# sistem_minimum_Atmega8.net
KiCad netlist of a schematic drawn in EAGLE
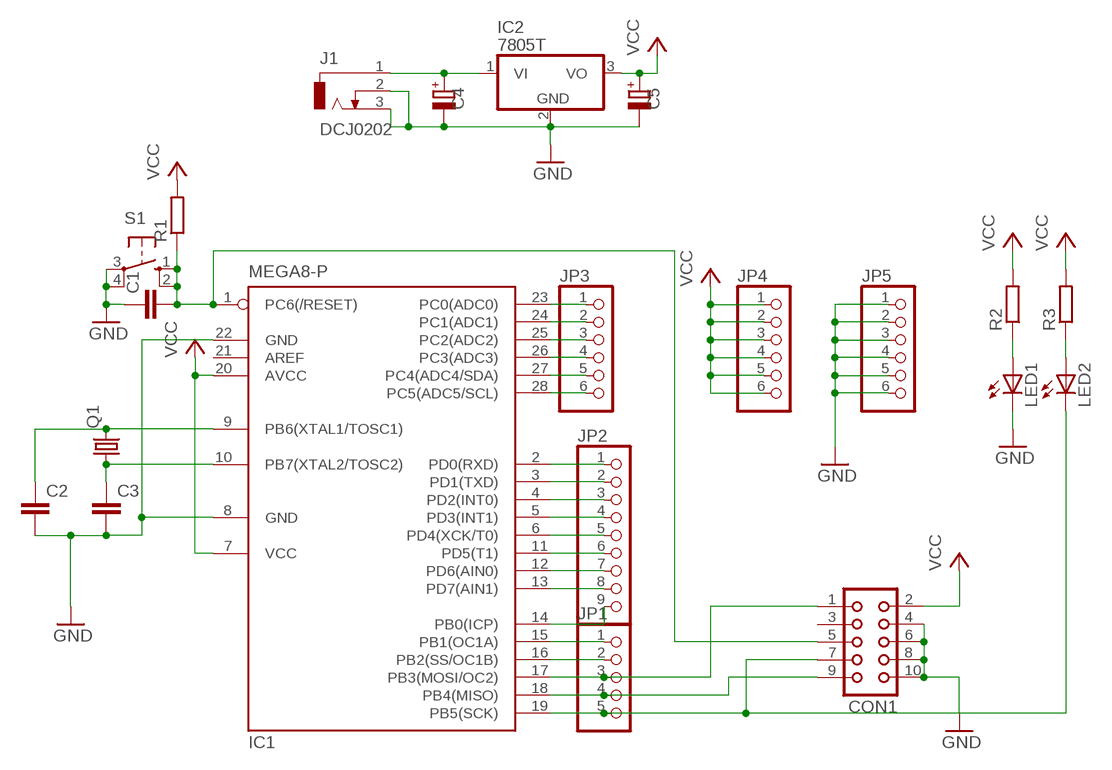
[diagram p0: schematic, sheet 1]

(export (version "E")
  (design (tool "Eeschema 10.0.6"))
  (components
    (comp (ref "C1")
      (value "C-EU025-030X050")
      (footprint "eagle-import:C025-030X050")
      (libsource (lib "eagle-import") (part "C-EU025-030X050"))
    )
    (comp (ref "C2")
      (value "C-EU025-030X050")
      (footprint "eagle-import:C025-030X050")
      (libsource (lib "eagle-import") (part "C-EU025-030X050"))
    )
    (comp (ref "C3")
      (value "C-EU025-030X050")
      (footprint "eagle-import:C025-030X050")
      (libsource (lib "eagle-import") (part "C-EU025-030X050"))
    )
    (comp (ref "C4")
      (value "CPOL-EUE2.5-6")
      (footprint "eagle-import:E2,5-6")
      (libsource (lib "eagle-import") (part "CPOL-EUE2.5-6"))
    )
    (comp (ref "C5")
      (value "CPOL-EUE2.5-6")
      (footprint "eagle-import:E2,5-6")
      (libsource (lib "eagle-import") (part "CPOL-EUE2.5-6"))
    )
    (comp (ref "CON1")
      (value "CON10")
      (footprint "eagle-import:CON10")
      (libsource (lib "eagle-import") (part "CON10"))
    )
    (comp (ref "IC1")
      (value "MEGA8-P")
      (footprint "eagle-import:DIL28-3")
      (libsource (lib "eagle-import") (part "MEGA8-P"))
    )
    (comp (ref "IC2")
      (value "7805T")
      (footprint "eagle-import:TO220H")
      (libsource (lib "eagle-import") (part "78T05"))
    )
    (comp (ref "J1")
      (value "DCJ0202")
      (footprint "eagle-import:DCJ0202")
      (libsource (lib "eagle-import") (part "DCJ0202"))
    )
    (comp (ref "JP1")
      (value "PINHD-1X5")
      (footprint "eagle-import:1X05")
      (libsource (lib "eagle-import") (part "PINHD-1X5"))
    )
    (comp (ref "JP2")
      (value "PINHD-1X9")
      (footprint "eagle-import:1X09")
      (libsource (lib "eagle-import") (part "PINHD-1X9"))
    )
    (comp (ref "JP3")
      (value "PINHD-1X6")
      (footprint "eagle-import:1X06")
      (libsource (lib "eagle-import") (part "PINHD-1X6"))
    )
    (comp (ref "JP4")
      (value "PINHD-1X6")
      (footprint "eagle-import:1X06")
      (libsource (lib "eagle-import") (part "pinhead_325_PINHD-1X6"))
    )
    (comp (ref "JP5")
      (value "PINHD-1X6")
      (footprint "eagle-import:1X06")
      (libsource (lib "eagle-import") (part "pinhead_325_PINHD-1X6"))
    )
    (comp (ref "LED1")
      (value "LED3MM")
      (footprint "eagle-import:LED3MM")
      (libsource (lib "eagle-import") (part "LED3MM"))
    )
    (comp (ref "LED2")
      (value "LED3MM")
      (footprint "eagle-import:LED3MM")
      (libsource (lib "eagle-import") (part "LED3MM"))
    )
    (comp (ref "Q1")
      (value "CRYSTALHC49U-V")
      (footprint "eagle-import:HC49U-V")
      (libsource (lib "eagle-import") (part "CRYSTALHC49U-V"))
    )
    (comp (ref "R1")
      (value "R-EU_0204/7")
      (footprint "eagle-import:0204_7")
      (libsource (lib "eagle-import") (part "R-EU_0204/7"))
    )
    (comp (ref "R2")
      (value "R-EU_0204/7")
      (footprint "eagle-import:0204_7")
      (libsource (lib "eagle-import") (part "R-EU_0204/7"))
    )
    (comp (ref "R3")
      (value "R-EU_0204/7")
      (footprint "eagle-import:0204_7")
      (libsource (lib "eagle-import") (part "R-EU_0204/7"))
    )
    (comp (ref "S1")
      (value "10-XX")
      (footprint "eagle-import:B3F-10XX")
      (fields (field (name "MPN") "B3F-1000"))
      (libsource (lib "eagle-import") (part "10-XX"))
    )
  )
  (nets
    (net (code "1") (name "GND") (class "Default")
      (node (ref "C1") (pin "1") (pinfunction "1_1") (pintype "passive"))
      (node (ref "C2") (pin "2") (pinfunction "2_2") (pintype "passive"))
      (node (ref "C3") (pin "2") (pinfunction "2_2") (pintype "passive"))
      (node (ref "C4") (pin "-") (pinfunction "-_-") (pintype "passive"))
      (node (ref "C5") (pin "-") (pinfunction "-_-") (pintype "passive"))
      (node (ref "CON1") (pin "10") (pinfunction "10_10") (pintype "passive"))
      (node (ref "CON1") (pin "4") (pinfunction "4_4") (pintype "passive"))
      (node (ref "CON1") (pin "6") (pinfunction "6_6") (pintype "passive"))
      (node (ref "CON1") (pin "8") (pinfunction "8_8") (pintype "passive"))
      (node (ref "IC1") (pin "22") (pinfunction "GND_22") (pintype "power_in"))
      (node (ref "IC1") (pin "8") (pinfunction "GND_8") (pintype "power_in"))
      (node (ref "IC2") (pin "2") (pinfunction "GND_2") (pintype "passive"))
      (node (ref "J1") (pin "2") (pinfunction "2_2") (pintype "passive"))
      (node (ref "J1") (pin "3") (pinfunction "3_3") (pintype "passive"))
      (node (ref "JP5") (pin "1") (pinfunction "1_1") (pintype "passive"))
      (node (ref "JP5") (pin "2") (pinfunction "2_2") (pintype "passive"))
      (node (ref "JP5") (pin "3") (pinfunction "3_3") (pintype "passive"))
      (node (ref "JP5") (pin "4") (pinfunction "4_4") (pintype "passive"))
      (node (ref "JP5") (pin "5") (pinfunction "5_5") (pintype "passive"))
      (node (ref "JP5") (pin "6") (pinfunction "6_6") (pintype "passive"))
      (node (ref "LED1") (pin "K") (pinfunction "C_K") (pintype "passive"))
      (node (ref "S1") (pin "3") (pinfunction "P_3") (pintype "passive"))
      (node (ref "S1") (pin "4") (pinfunction "P1_4") (pintype "passive"))
    )
    (net (code "2") (name "Net-(IC1-PB0(ICP))") (class "Default")
      (node (ref "IC1") (pin "14") (pinfunction "PB0(ICP)_14") (pintype "bidirectional"))
      (node (ref "JP2") (pin "9") (pinfunction "9_9") (pintype "passive"))
    )
    (net (code "3") (name "Net-(IC1-PB1(OC1A))") (class "Default")
      (node (ref "IC1") (pin "15") (pinfunction "PB1(OC1A)_15") (pintype "bidirectional"))
      (node (ref "JP1") (pin "1") (pinfunction "1_1") (pintype "passive"))
    )
    (net (code "4") (name "Net-(IC1-PB2(SS{slash}OC1B))") (class "Default")
      (node (ref "IC1") (pin "16") (pinfunction "PB2(SS/OC1B)_16") (pintype "bidirectional"))
      (node (ref "JP1") (pin "2") (pinfunction "2_2") (pintype "passive"))
    )
    (net (code "5") (name "Net-(IC1-PB3(MOSI{slash}OC2))") (class "Default")
      (node (ref "CON1") (pin "1") (pinfunction "1_1") (pintype "passive"))
      (node (ref "IC1") (pin "17") (pinfunction "PB3(MOSI/OC2)_17") (pintype "bidirectional"))
      (node (ref "JP1") (pin "3") (pinfunction "3_3") (pintype "passive"))
    )
    (net (code "6") (name "Net-(IC1-PB4(MISO))") (class "Default")
      (node (ref "CON1") (pin "9") (pinfunction "9_9") (pintype "passive"))
      (node (ref "IC1") (pin "18") (pinfunction "PB4(MISO)_18") (pintype "bidirectional"))
      (node (ref "JP1") (pin "4") (pinfunction "4_4") (pintype "passive"))
    )
    (net (code "7") (name "Net-(IC1-PB5(SCK))") (class "Default")
      (node (ref "CON1") (pin "7") (pinfunction "7_7") (pintype "passive"))
      (node (ref "IC1") (pin "19") (pinfunction "PB5(SCK)_19") (pintype "bidirectional"))
      (node (ref "JP1") (pin "5") (pinfunction "5_5") (pintype "passive"))
      (node (ref "LED2") (pin "K") (pinfunction "C_K") (pintype "passive"))
    )
    (net (code "8") (name "Net-(IC1-PB6(XTAL1{slash}TOSC1))") (class "Default")
      (node (ref "C2") (pin "1") (pinfunction "1_1") (pintype "passive"))
      (node (ref "IC1") (pin "9") (pinfunction "PB6(XTAL1/TOSC1)_9") (pintype "bidirectional"))
      (node (ref "Q1") (pin "2") (pinfunction "2_2") (pintype "passive"))
    )
    (net (code "9") (name "Net-(IC1-PB7(XTAL2{slash}TOSC2))") (class "Default")
      (node (ref "C3") (pin "1") (pinfunction "1_1") (pintype "passive"))
      (node (ref "IC1") (pin "10") (pinfunction "PB7(XTAL2/TOSC2)_10") (pintype "bidirectional"))
      (node (ref "Q1") (pin "1") (pinfunction "1_1") (pintype "passive"))
    )
    (net (code "10") (name "Net-(IC1-PC0(ADC0))") (class "Default")
      (node (ref "IC1") (pin "23") (pinfunction "PC0(ADC0)_23") (pintype "bidirectional"))
      (node (ref "JP3") (pin "1") (pinfunction "1_1") (pintype "passive"))
    )
    (net (code "11") (name "Net-(IC1-PC1(ADC1))") (class "Default")
      (node (ref "IC1") (pin "24") (pinfunction "PC1(ADC1)_24") (pintype "bidirectional"))
      (node (ref "JP3") (pin "2") (pinfunction "2_2") (pintype "passive"))
    )
    (net (code "12") (name "Net-(IC1-PC2(ADC2))") (class "Default")
      (node (ref "IC1") (pin "25") (pinfunction "PC2(ADC2)_25") (pintype "bidirectional"))
      (node (ref "JP3") (pin "3") (pinfunction "3_3") (pintype "passive"))
    )
    (net (code "13") (name "Net-(IC1-PC3(ADC3))") (class "Default")
      (node (ref "IC1") (pin "26") (pinfunction "PC3(ADC3)_26") (pintype "bidirectional"))
      (node (ref "JP3") (pin "4") (pinfunction "4_4") (pintype "passive"))
    )
    (net (code "14") (name "Net-(IC1-PC4(ADC4{slash}SDA))") (class "Default")
      (node (ref "IC1") (pin "27") (pinfunction "PC4(ADC4/SDA)_27") (pintype "bidirectional"))
      (node (ref "JP3") (pin "5") (pinfunction "5_5") (pintype "passive"))
    )
    (net (code "15") (name "Net-(IC1-PC5(ADC5{slash}SCL))") (class "Default")
      (node (ref "IC1") (pin "28") (pinfunction "PC5(ADC5/SCL)_28") (pintype "bidirectional"))
      (node (ref "JP3") (pin "6") (pinfunction "6_6") (pintype "passive"))
    )
    (net (code "16") (name "Net-(IC1-PC6({slash}RESET))") (class "Default")
      (node (ref "C1") (pin "2") (pinfunction "2_2") (pintype "passive"))
      (node (ref "CON1") (pin "5") (pinfunction "5_5") (pintype "passive"))
      (node (ref "IC1") (pin "1") (pinfunction "PC6(/RESET)_1") (pintype "bidirectional"))
      (node (ref "R1") (pin "1") (pinfunction "1_1") (pintype "passive"))
      (node (ref "S1") (pin "1") (pinfunction "S_1") (pintype "passive"))
      (node (ref "S1") (pin "2") (pinfunction "S1_2") (pintype "passive"))
    )
    (net (code "17") (name "Net-(IC1-PD0(RXD))") (class "Default")
      (node (ref "IC1") (pin "2") (pinfunction "PD0(RXD)_2") (pintype "bidirectional"))
      (node (ref "JP2") (pin "1") (pinfunction "1_1") (pintype "passive"))
    )
    (net (code "18") (name "Net-(IC1-PD1(TXD))") (class "Default")
      (node (ref "IC1") (pin "3") (pinfunction "PD1(TXD)_3") (pintype "bidirectional"))
      (node (ref "JP2") (pin "2") (pinfunction "2_2") (pintype "passive"))
    )
    (net (code "19") (name "Net-(IC1-PD2(INT0))") (class "Default")
      (node (ref "IC1") (pin "4") (pinfunction "PD2(INT0)_4") (pintype "bidirectional"))
      (node (ref "JP2") (pin "3") (pinfunction "3_3") (pintype "passive"))
    )
    (net (code "20") (name "Net-(IC1-PD3(INT1))") (class "Default")
      (node (ref "IC1") (pin "5") (pinfunction "PD3(INT1)_5") (pintype "bidirectional"))
      (node (ref "JP2") (pin "4") (pinfunction "4_4") (pintype "passive"))
    )
    (net (code "21") (name "Net-(IC1-PD4(XCK{slash}T0))") (class "Default")
      (node (ref "IC1") (pin "6") (pinfunction "PD4(XCK/T0)_6") (pintype "bidirectional"))
      (node (ref "JP2") (pin "5") (pinfunction "5_5") (pintype "passive"))
    )
    (net (code "22") (name "Net-(IC1-PD5(T1))") (class "Default")
      (node (ref "IC1") (pin "11") (pinfunction "PD5(T1)_11") (pintype "bidirectional"))
      (node (ref "JP2") (pin "6") (pinfunction "6_6") (pintype "passive"))
    )
    (net (code "23") (name "Net-(IC1-PD6(AIN0))") (class "Default")
      (node (ref "IC1") (pin "12") (pinfunction "PD6(AIN0)_12") (pintype "bidirectional"))
      (node (ref "JP2") (pin "7") (pinfunction "7_7") (pintype "passive"))
    )
    (net (code "24") (name "Net-(IC1-PD7(AIN1))") (class "Default")
      (node (ref "IC1") (pin "13") (pinfunction "PD7(AIN1)_13") (pintype "bidirectional"))
      (node (ref "JP2") (pin "8") (pinfunction "8_8") (pintype "passive"))
    )
    (net (code "25") (name "Net-(IC2-VI)") (class "Default")
      (node (ref "C4") (pin "+") (pinfunction "+_+") (pintype "passive"))
      (node (ref "IC2") (pin "1") (pinfunction "VI_1") (pintype "input"))
      (node (ref "J1") (pin "1") (pinfunction "1_1") (pintype "passive"))
    )
    (net (code "26") (name "Net-(LED1-PadA)") (class "Default")
      (node (ref "LED1") (pin "A") (pinfunction "A_A") (pintype "passive"))
      (node (ref "R2") (pin "1") (pinfunction "1_1") (pintype "passive"))
    )
    (net (code "27") (name "Net-(LED2-PadA)") (class "Default")
      (node (ref "LED2") (pin "A") (pinfunction "A_A") (pintype "passive"))
      (node (ref "R3") (pin "1") (pinfunction "1_1") (pintype "passive"))
    )
    (net (code "28") (name "VCC") (class "Default")
      (node (ref "C5") (pin "+") (pinfunction "+_+") (pintype "passive"))
      (node (ref "CON1") (pin "2") (pinfunction "2_2") (pintype "passive"))
      (node (ref "IC1") (pin "20") (pinfunction "AVCC_20") (pintype "power_in"))
      (node (ref "IC1") (pin "7") (pinfunction "VCC_7") (pintype "power_in"))
      (node (ref "IC2") (pin "3") (pinfunction "VO_3") (pintype "passive"))
      (node (ref "JP4") (pin "1") (pinfunction "1_1") (pintype "passive"))
      (node (ref "JP4") (pin "2") (pinfunction "2_2") (pintype "passive"))
      (node (ref "JP4") (pin "3") (pinfunction "3_3") (pintype "passive"))
      (node (ref "JP4") (pin "4") (pinfunction "4_4") (pintype "passive"))
      (node (ref "JP4") (pin "5") (pinfunction "5_5") (pintype "passive"))
      (node (ref "JP4") (pin "6") (pinfunction "6_6") (pintype "passive"))
      (node (ref "R1") (pin "2") (pinfunction "2_2") (pintype "passive"))
      (node (ref "R2") (pin "2") (pinfunction "2_2") (pintype "passive"))
      (node (ref "R3") (pin "2") (pinfunction "2_2") (pintype "passive"))
    )
    (net (code "29") (name "unconnected-(CON1-Pad3)") (class "Default")
      (node (ref "CON1") (pin "3") (pinfunction "3_3") (pintype "passive"))
    )
    (net (code "30") (name "unconnected-(IC1-AREF-Pad21)") (class "Default")
      (node (ref "IC1") (pin "21") (pinfunction "AREF_21") (pintype "passive"))
    )
  )
)
